# tunnelAmp.net
KiCad netlist of a schematic drawn in EAGLE
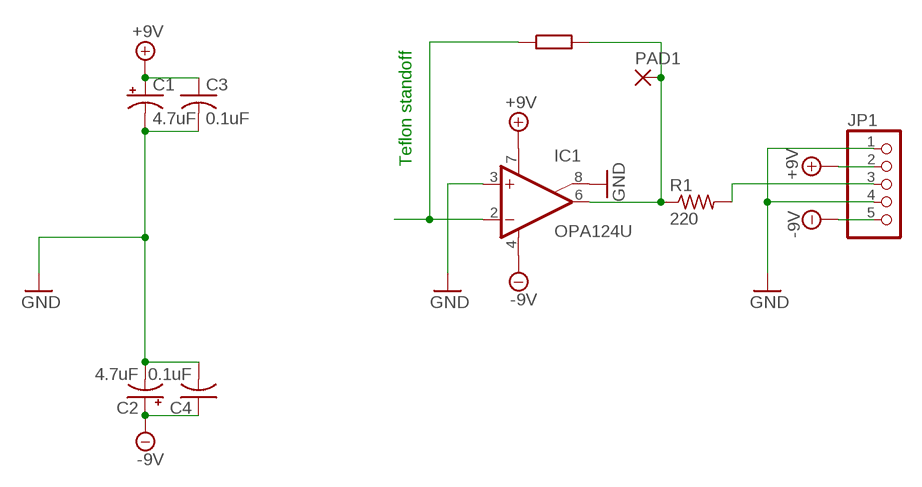
[diagram p0: schematic, sheet 1]

(export (version "E")
  (design (tool "Eeschema 10.0.6"))
  (components
    (comp (ref "C1")
      (value "4.7uF")
      (footprint "eagle-import:C_6032-28W")
      (libsource (lib "eagle-import") (part "CPOL-USC/6032-28W"))
    )
    (comp (ref "C2")
      (value "4.7uF")
      (footprint "eagle-import:C_6032-28W")
      (libsource (lib "eagle-import") (part "CPOL-USC/6032-28W"))
    )
    (comp (ref "C3")
      (value "0.1uF")
      (footprint "eagle-import:C0603")
      (libsource (lib "eagle-import") (part "C-USC0603"))
    )
    (comp (ref "C4")
      (value "0.1uF")
      (footprint "eagle-import:C0603")
      (libsource (lib "eagle-import") (part "C-USC0603"))
    )
    (comp (ref "IC1")
      (value "OPA124U")
      (footprint "eagle-import:SO08")
      (libsource (lib "eagle-import") (part "OPA124U"))
    )
    (comp (ref "JP1")
      (value "PINHD-1X5")
      (footprint "eagle-import:1X05")
      (libsource (lib "eagle-import") (part "PINHD-1X5"))
    )
    (comp (ref "PAD1")
      (value "1,6/0,9")
      (footprint "eagle-import:1,6_0,9")
      (libsource (lib "eagle-import") (part "1,6/0,9"))
    )
    (comp (ref "R1")
      (value "220")
      (footprint "eagle-import:R0603")
      (libsource (lib "eagle-import") (part "R-US_R0603"))
    )
  )
  (nets
    (net (code "1") (name "+9V") (class "Default")
      (node (ref "C1") (pin "+") (pinfunction "+_+") (pintype "passive"))
      (node (ref "C3") (pin "1") (pinfunction "1_1") (pintype "passive"))
      (node (ref "IC1") (pin "7") (pinfunction "V+_7") (pintype "power_in"))
      (node (ref "JP1") (pin "2") (pinfunction "2_2") (pintype "passive"))
    )
    (net (code "2") (name "-9V") (class "Default")
      (node (ref "C2") (pin "+") (pinfunction "+_+") (pintype "passive"))
      (node (ref "C4") (pin "1") (pinfunction "1_1") (pintype "passive"))
      (node (ref "IC1") (pin "4") (pinfunction "V-_4") (pintype "power_in"))
      (node (ref "JP1") (pin "5") (pinfunction "5_5") (pintype "passive"))
    )
    (net (code "3") (name "GND") (class "Default")
      (node (ref "C1") (pin "-") (pinfunction "-_-") (pintype "passive"))
      (node (ref "C2") (pin "-") (pinfunction "-_-") (pintype "passive"))
      (node (ref "C3") (pin "2") (pinfunction "2_2") (pintype "passive"))
      (node (ref "C4") (pin "2") (pinfunction "2_2") (pintype "passive"))
      (node (ref "IC1") (pin "3") (pinfunction "+IN_3") (pintype "input"))
      (node (ref "IC1") (pin "8") (pinfunction "SUBS_8") (pintype "passive"))
      (node (ref "JP1") (pin "1") (pinfunction "1_1") (pintype "passive"))
      (node (ref "JP1") (pin "4") (pinfunction "4_4") (pintype "passive"))
    )
    (net (code "4") (name "Net-(IC1-OUT)") (class "Default")
      (node (ref "IC1") (pin "6") (pinfunction "OUT_6") (pintype "output"))
      (node (ref "PAD1") (pin "1") (pinfunction "P_1") (pintype "passive"))
      (node (ref "R1") (pin "1") (pinfunction "1_1") (pintype "passive"))
    )
    (net (code "5") (name "Net-(JP1-Pad3)") (class "Default")
      (node (ref "JP1") (pin "3") (pinfunction "3_3") (pintype "passive"))
      (node (ref "R1") (pin "2") (pinfunction "2_2") (pintype "passive"))
    )
    (net (code "6") (name "unconnected-(IC1--IN-Pad2)") (class "Default")
      (node (ref "IC1") (pin "2") (pinfunction "-IN_2") (pintype "input"))
    )
  )
)
